# H-00488_-_Connectors.net
KiCad netlist of a schematic drawn in Altium Designer
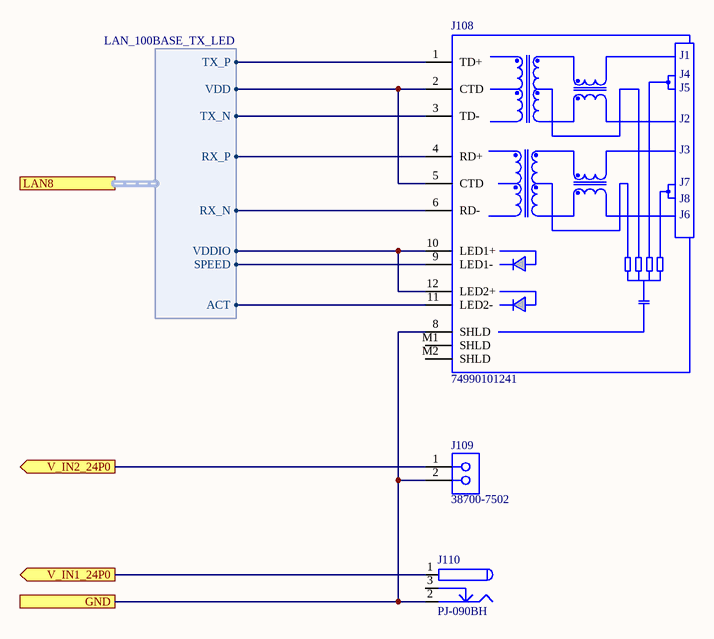
[diagram p0: H-00488 - Connectors.SchDoc]

(export (version "E")
  (design (tool "Eeschema 10.0.6"))
  (components
    (comp (ref "J108")
      (value "74990101241")
      (footprint "WURTH_74990101241")
      (description "Datacom Transformer")
      (libsource (lib "Hiber") (part "74990101241"))
    )
    (comp (ref "J109")
      (value "38700-7502")
      (footprint "MOLEX_387007502")
      (description "Barrier Strip Terminal Block, 1 Row(s), 1 Deck(s)")
      (fields (field (name "SAFETY APPROVAL") "UL,CSA"))
      (libsource (lib "Hiber") (part "HEADER-FEMALE-01X02"))
    )
    (comp (ref "J110")
      (value "PJ-090BH")
      (footprint "CUI_PJ-090BH")
      (description "Circular DC Power Connector")
      (libsource (lib "Hiber") (part "BARREL-JACK-MALE-3P"))
    )
  )
  (nets
    (net (code "2") (name "/ACT") (class "Default")
      (node (ref "J108") (pin "11") (pinfunction "LED2-_11") (pintype "passive"))
    )
    (net (code "3") (name "/GND") (class "Default")
      (node (ref "J108") (pin "8") (pinfunction "SHLD_8") (pintype "passive"))
      (node (ref "J109") (pin "2") (pinfunction "2_2") (pintype "passive"))
      (node (ref "J110") (pin "2") (pinfunction "2_2") (pintype "power_in"))
    )
    (net (code "4") (name "/RX_N") (class "Default")
      (node (ref "J108") (pin "6") (pinfunction "RD-_6") (pintype "passive"))
    )
    (net (code "5") (name "/RX_P") (class "Default")
      (node (ref "J108") (pin "4") (pinfunction "RD+_4") (pintype "passive"))
    )
    (net (code "6") (name "/SPEED") (class "Default")
      (node (ref "J108") (pin "9") (pinfunction "LED1-_9") (pintype "passive"))
    )
    (net (code "7") (name "/TX_N") (class "Default")
      (node (ref "J108") (pin "3") (pinfunction "TD-_3") (pintype "passive"))
    )
    (net (code "8") (name "/TX_P") (class "Default")
      (node (ref "J108") (pin "1") (pinfunction "TD+_1") (pintype "passive"))
    )
    (net (code "9") (name "/VDD") (class "Default")
      (node (ref "J108") (pin "2") (pinfunction "CTD_2") (pintype "passive"))
      (node (ref "J108") (pin "5") (pinfunction "CTD_5") (pintype "passive"))
    )
    (net (code "10") (name "/VDDIO") (class "Default")
      (node (ref "J108") (pin "10") (pinfunction "LED1+_10") (pintype "passive"))
      (node (ref "J108") (pin "12") (pinfunction "LED2+_12") (pintype "passive"))
    )
    (net (code "11") (name "/V_IN1_24P0") (class "Default")
      (node (ref "J110") (pin "1") (pinfunction "1_1") (pintype "power_in"))
    )
    (net (code "12") (name "/V_IN2_24P0") (class "Default")
      (node (ref "J109") (pin "1") (pinfunction "1_1") (pintype "passive"))
    )
    (net (code "14") (name "unconnected-(J108-SHLD-PadM1)") (class "Default")
      (node (ref "J108") (pin "M1") (pinfunction "SHLD_M1") (pintype "passive"))
    )
    (net (code "15") (name "unconnected-(J108-SHLD-PadM2)") (class "Default")
      (node (ref "J108") (pin "M2") (pinfunction "SHLD_M2") (pintype "passive"))
    )
    (net (code "16") (name "unconnected-(J110-Pad3)") (class "Default")
      (node (ref "J110") (pin "3") (pinfunction "3_3") (pintype "power_in"))
    )
  )
)
